# ALMOST4ALLMINI.net
KiCad netlist of a schematic drawn in EAGLE
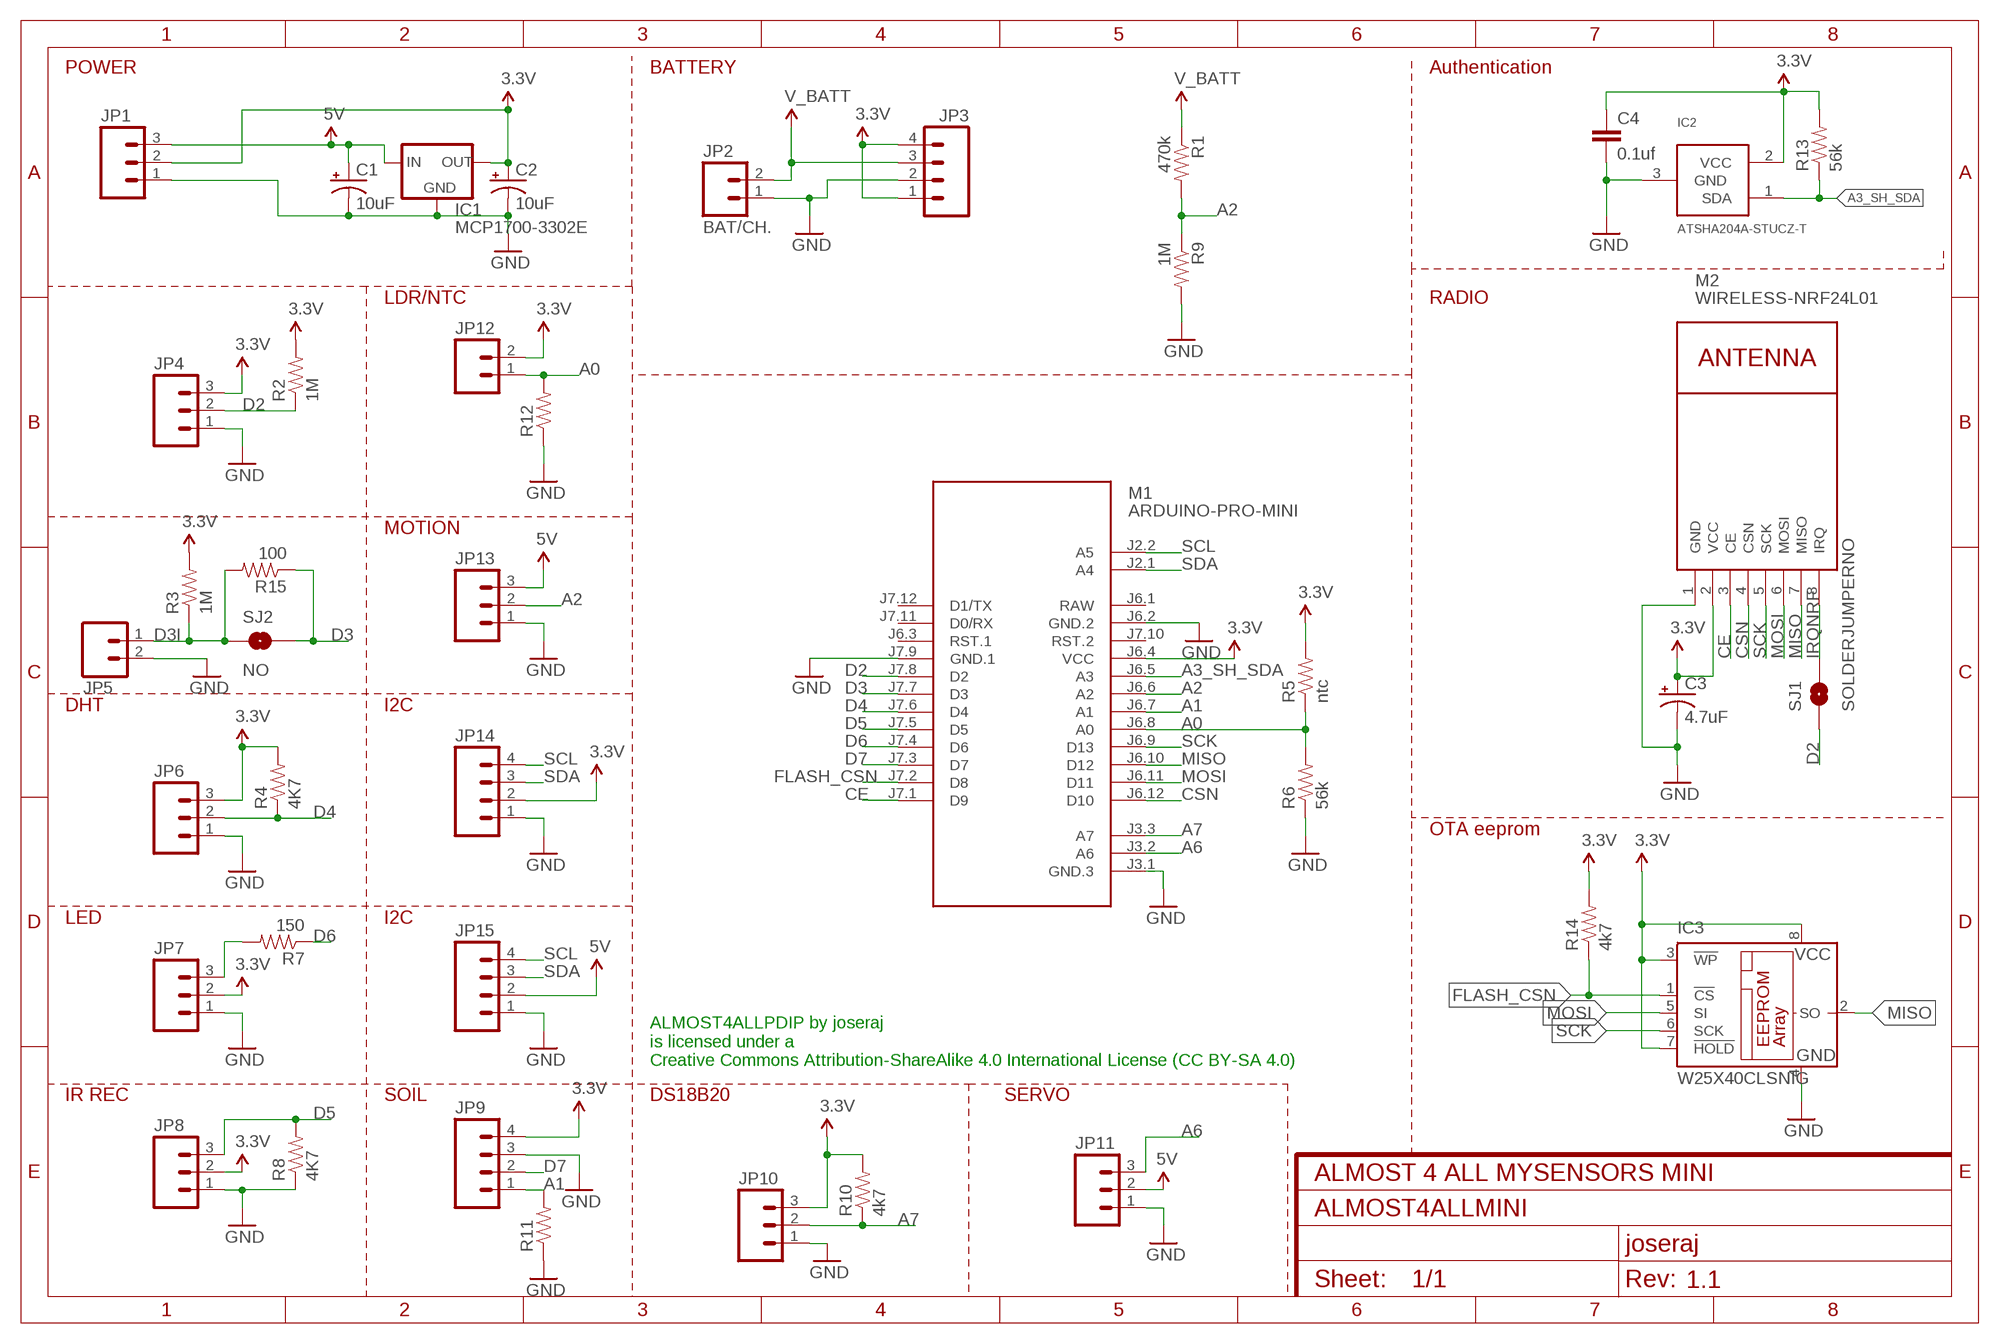
[diagram p0: schematic, sheet 1]

(export (version "E")
  (design (tool "Eeschema 10.0.6"))
  (components
    (comp (ref "C1")
      (value "10uF")
      (footprint "eagle-import:CPOL-RADIAL-10UF-25V")
      (libsource (lib "eagle-import") (part "CAP_POLPTH2"))
    )
    (comp (ref "C2")
      (value "10uF")
      (footprint "eagle-import:CPOL-RADIAL-10UF-25V")
      (libsource (lib "eagle-import") (part "CAP_POLPTH2"))
    )
    (comp (ref "C3")
      (value "4.7uF")
      (footprint "eagle-import:CPOL-RADIAL-10UF-25V")
      (libsource (lib "eagle-import") (part "CAP_POLPTH2"))
    )
    (comp (ref "C4")
      (value "0.1uf")
      (footprint "eagle-import:0805")
      (libsource (lib "eagle-import") (part "CAP0805"))
    )
    (comp (ref "IC1")
      (value "MCP1700-3302E")
      (footprint "eagle-import:TO92")
      (libsource (lib "eagle-import") (part "MCP1700TRI"))
    )
    (comp (ref "IC2")
      (value "ATSHA204A-STUCZ-T")
      (footprint "eagle-import:SOT23")
      (libsource (lib "eagle-import") (part "ATSHA204A"))
    )
    (comp (ref "IC3")
      (value "W25X40CLSNIG")
      (footprint "eagle-import:SO-08")
      (fields (field (name "MF") "MICROCHIP") (field (name "MPN") "25LC080/SN"))
      (libsource (lib "eagle-import") (part "25SNLC080"))
    )
    (comp (ref "JP1")
      (value "M03POLAR_LOCK")
      (footprint "eagle-import:MOLEX-1X3_LOCK")
      (libsource (lib "eagle-import") (part "M03POLAR_LOCK"))
    )
    (comp (ref "JP2")
      (value "BAT/CH.")
      (footprint "eagle-import:MOLEX-1X2_LOCK")
      (libsource (lib "eagle-import") (part "M02POLAR_LOCK"))
    )
    (comp (ref "JP3")
      (value "M04NO_SILK_ALL_ROUND")
      (footprint "eagle-import:1X04_NO_SILK_ALL_ROUND")
      (libsource (lib "eagle-import") (part "M04NO_SILK_ALL_ROUND"))
    )
    (comp (ref "JP4")
      (value "M03POLAR_LOCK")
      (footprint "eagle-import:MOLEX-1X3_LOCK")
      (libsource (lib "eagle-import") (part "M03POLAR_LOCK"))
    )
    (comp (ref "JP5")
      (value "M02POLAR_LOCK")
      (footprint "eagle-import:MOLEX-1X2_LOCK")
      (libsource (lib "eagle-import") (part "M02POLAR_LOCK"))
    )
    (comp (ref "JP6")
      (value "M03POLAR_LOCK")
      (footprint "eagle-import:MOLEX-1X3_LOCK")
      (libsource (lib "eagle-import") (part "M03POLAR_LOCK"))
    )
    (comp (ref "JP7")
      (value "M03POLAR_LOCK")
      (footprint "eagle-import:MOLEX-1X3_LOCK")
      (libsource (lib "eagle-import") (part "M03POLAR_LOCK"))
    )
    (comp (ref "JP8")
      (value "M03POLAR_LOCK")
      (footprint "eagle-import:MOLEX-1X3_LOCK")
      (libsource (lib "eagle-import") (part "M03POLAR_LOCK"))
    )
    (comp (ref "JP9")
      (value "M04POLAR_LOCK")
      (footprint "eagle-import:MOLEX-1X4_LOCK")
      (libsource (lib "eagle-import") (part "M04POLAR_LOCK"))
    )
    (comp (ref "JP10")
      (value "M03POLAR_LOCK")
      (footprint "eagle-import:MOLEX-1X3_LOCK")
      (libsource (lib "eagle-import") (part "M03POLAR_LOCK"))
    )
    (comp (ref "JP11")
      (value "M03POLAR_LOCK")
      (footprint "eagle-import:MOLEX-1X3_LOCK")
      (libsource (lib "eagle-import") (part "M03POLAR_LOCK"))
    )
    (comp (ref "JP12")
      (value "M02POLAR_LOCK")
      (footprint "eagle-import:MOLEX-1X2_LOCK")
      (libsource (lib "eagle-import") (part "M02POLAR_LOCK"))
    )
    (comp (ref "JP13")
      (value "M03POLAR_LOCK")
      (footprint "eagle-import:MOLEX-1X3_LOCK")
      (libsource (lib "eagle-import") (part "M03POLAR_LOCK"))
    )
    (comp (ref "JP14")
      (value "M04POLAR_LOCK")
      (footprint "eagle-import:MOLEX-1X4_LOCK")
      (libsource (lib "eagle-import") (part "M04POLAR_LOCK"))
    )
    (comp (ref "JP15")
      (value "M04POLAR_LOCK")
      (footprint "eagle-import:MOLEX-1X4_LOCK")
      (libsource (lib "eagle-import") (part "M04POLAR_LOCK"))
    )
    (comp (ref "M1")
      (value "ARDUINO-PRO-MINI")
      (footprint "eagle-import:ARDUINO-PRO-MINI#NP")
      (libsource (lib "eagle-import") (part "ARDUINO-PRO-MINI-#NP3.3V"))
    )
    (comp (ref "M2")
      (value "WIRELESS-NRF24L01")
      (footprint "eagle-import:WIRELESS-NRF24L01")
      (libsource (lib "eagle-import") (part "WIRELESS-NRF24L01"))
    )
    (comp (ref "R1")
      (value "470k")
      (footprint "eagle-import:0805")
      (libsource (lib "eagle-import") (part "RESISTOR0805-RES"))
    )
    (comp (ref "R2")
      (value "1M")
      (footprint "eagle-import:0805")
      (libsource (lib "eagle-import") (part "RESISTOR0805-RES"))
    )
    (comp (ref "R3")
      (value "1M")
      (footprint "eagle-import:0805")
      (libsource (lib "eagle-import") (part "RESISTOR0805-RES"))
    )
    (comp (ref "R4")
      (value "4K7")
      (footprint "eagle-import:0805")
      (libsource (lib "eagle-import") (part "RESISTOR0805-RES"))
    )
    (comp (ref "R5")
      (value "ntc")
      (footprint "eagle-import:0805")
      (libsource (lib "eagle-import") (part "RESISTOR0805-RES"))
    )
    (comp (ref "R6")
      (value "56k")
      (footprint "eagle-import:0805")
      (libsource (lib "eagle-import") (part "RESISTOR0805-RES"))
    )
    (comp (ref "R7")
      (value "150")
      (footprint "eagle-import:0805")
      (libsource (lib "eagle-import") (part "RESISTOR0805-RES"))
    )
    (comp (ref "R8")
      (value "4K7")
      (footprint "eagle-import:0805")
      (libsource (lib "eagle-import") (part "RESISTOR0805-RES"))
    )
    (comp (ref "R9")
      (value "1M")
      (footprint "eagle-import:0805")
      (libsource (lib "eagle-import") (part "RESISTOR0805-RES"))
    )
    (comp (ref "R10")
      (value "4k7")
      (footprint "eagle-import:0805")
      (libsource (lib "eagle-import") (part "RESISTOR0805-RES"))
    )
    (comp (ref "R11")
      (value "RESISTOR0805-RES")
      (footprint "eagle-import:0805")
      (libsource (lib "eagle-import") (part "RESISTOR0805-RES"))
    )
    (comp (ref "R12")
      (value "RESISTOR0805-RES")
      (footprint "eagle-import:0805")
      (libsource (lib "eagle-import") (part "RESISTOR0805-RES"))
    )
    (comp (ref "R13")
      (value "56k")
      (footprint "eagle-import:0805")
      (libsource (lib "eagle-import") (part "RESISTOR0805-RES"))
    )
    (comp (ref "R14")
      (value "4k7")
      (footprint "eagle-import:0805")
      (libsource (lib "eagle-import") (part "RESISTOR0805-RES"))
    )
    (comp (ref "R15")
      (value "100")
      (footprint "eagle-import:0805")
      (libsource (lib "eagle-import") (part "RESISTOR0805-RES"))
    )
    (comp (ref "SJ1")
      (value "SOLDERJUMPERNO")
      (footprint "eagle-import:SJ_2S-NO")
      (libsource (lib "eagle-import") (part "SOLDERJUMPERNO"))
    )
    (comp (ref "SJ2")
      (value "NO")
      (footprint "eagle-import:SJ_2S-NO")
      (libsource (lib "eagle-import") (part "SOLDERJUMPERNO"))
    )
  )
  (nets
    (net (code "1") (name "/A0") (class "Default")
      (node (ref "JP12") (pin "1") (pinfunction "1_1") (pintype "passive"))
      (node (ref "M1") (pin "J6.8") (pinfunction "A0_J6.8") (pintype "bidirectional"))
      (node (ref "R12") (pin "2") (pinfunction "2_2") (pintype "passive"))
      (node (ref "R5") (pin "1") (pinfunction "1_1") (pintype "passive"))
      (node (ref "R6") (pin "2") (pinfunction "2_2") (pintype "passive"))
    )
    (net (code "2") (name "/A1") (class "Default")
      (node (ref "JP9") (pin "1") (pinfunction "1_1") (pintype "passive"))
      (node (ref "M1") (pin "J6.7") (pinfunction "A1_J6.7") (pintype "bidirectional"))
      (node (ref "R11") (pin "2") (pinfunction "2_2") (pintype "passive"))
    )
    (net (code "3") (name "/A2") (class "Default")
      (node (ref "JP13") (pin "2") (pinfunction "2_2") (pintype "passive"))
      (node (ref "M1") (pin "J6.6") (pinfunction "A2_J6.6") (pintype "bidirectional"))
      (node (ref "R1") (pin "2") (pinfunction "2_2") (pintype "passive"))
      (node (ref "R9") (pin "1") (pinfunction "1_1") (pintype "passive"))
    )
    (net (code "4") (name "/A6") (class "Default")
      (node (ref "JP11") (pin "3") (pinfunction "3_3") (pintype "passive"))
      (node (ref "M1") (pin "J3.2") (pinfunction "A6_J3.2") (pintype "bidirectional"))
    )
    (net (code "5") (name "/A7") (class "Default")
      (node (ref "JP10") (pin "2") (pinfunction "2_2") (pintype "passive"))
      (node (ref "M1") (pin "J3.3") (pinfunction "A7_J3.3") (pintype "bidirectional"))
      (node (ref "R10") (pin "1") (pinfunction "1_1") (pintype "passive"))
    )
    (net (code "6") (name "/CE") (class "Default")
      (node (ref "M1") (pin "J7.1") (pinfunction "D9_J7.1") (pintype "bidirectional"))
      (node (ref "M2") (pin "3") (pinfunction "CE_3") (pintype "bidirectional"))
    )
    (net (code "7") (name "/CSN") (class "Default")
      (node (ref "M1") (pin "J6.12") (pinfunction "D10_J6.12") (pintype "bidirectional"))
      (node (ref "M2") (pin "4") (pinfunction "CSN_4") (pintype "bidirectional"))
    )
    (net (code "8") (name "/D2") (class "Default")
      (node (ref "JP4") (pin "2") (pinfunction "2_2") (pintype "passive"))
      (node (ref "M1") (pin "J7.8") (pinfunction "D2_J7.8") (pintype "bidirectional"))
      (node (ref "R2") (pin "1") (pinfunction "1_1") (pintype "passive"))
      (node (ref "SJ1") (pin "1") (pinfunction "1_1") (pintype "passive"))
    )
    (net (code "9") (name "/D3") (class "Default")
      (node (ref "M1") (pin "J7.7") (pinfunction "D3_J7.7") (pintype "bidirectional"))
      (node (ref "R15") (pin "1") (pinfunction "1_1") (pintype "passive"))
      (node (ref "SJ2") (pin "2") (pinfunction "2_2") (pintype "passive"))
    )
    (net (code "10") (name "/D3I") (class "Default")
      (node (ref "JP5") (pin "1") (pinfunction "1_1") (pintype "passive"))
      (node (ref "R15") (pin "2") (pinfunction "2_2") (pintype "passive"))
      (node (ref "R3") (pin "1") (pinfunction "1_1") (pintype "passive"))
      (node (ref "SJ2") (pin "1") (pinfunction "1_1") (pintype "passive"))
    )
    (net (code "11") (name "/D4") (class "Default")
      (node (ref "JP6") (pin "2") (pinfunction "2_2") (pintype "passive"))
      (node (ref "M1") (pin "J7.6") (pinfunction "D4_J7.6") (pintype "bidirectional"))
      (node (ref "R4") (pin "1") (pinfunction "1_1") (pintype "passive"))
    )
    (net (code "12") (name "/D5") (class "Default")
      (node (ref "JP8") (pin "3") (pinfunction "3_3") (pintype "passive"))
      (node (ref "M1") (pin "J7.5") (pinfunction "D5_J7.5") (pintype "bidirectional"))
      (node (ref "R8") (pin "2") (pinfunction "2_2") (pintype "passive"))
    )
    (net (code "13") (name "/D6") (class "Default")
      (node (ref "M1") (pin "J7.4") (pinfunction "D6_J7.4") (pintype "bidirectional"))
      (node (ref "R7") (pin "1") (pinfunction "1_1") (pintype "passive"))
    )
    (net (code "14") (name "/D7") (class "Default")
      (node (ref "JP9") (pin "2") (pinfunction "2_2") (pintype "passive"))
      (node (ref "M1") (pin "J7.3") (pinfunction "D7_J7.3") (pintype "bidirectional"))
    )
    (net (code "15") (name "/IRQNRF") (class "Default")
      (node (ref "M2") (pin "8") (pinfunction "IRQ_8") (pintype "bidirectional"))
      (node (ref "SJ1") (pin "2") (pinfunction "2_2") (pintype "passive"))
    )
    (net (code "16") (name "/RAW") (class "Default")
      (node (ref "M1") (pin "J6.1") (pinfunction "RAW_J6.1") (pintype "power_in"))
    )
    (net (code "17") (name "/SCL") (class "Default")
      (node (ref "JP14") (pin "4") (pinfunction "4_4") (pintype "passive"))
      (node (ref "JP15") (pin "4") (pinfunction "4_4") (pintype "passive"))
      (node (ref "M1") (pin "J2.2") (pinfunction "A5_J2.2") (pintype "bidirectional"))
    )
    (net (code "18") (name "/SDA") (class "Default")
      (node (ref "JP14") (pin "3") (pinfunction "3_3") (pintype "passive"))
      (node (ref "JP15") (pin "3") (pinfunction "3_3") (pintype "passive"))
      (node (ref "M1") (pin "J2.1") (pinfunction "A4_J2.1") (pintype "bidirectional"))
    )
    (net (code "19") (name "3.3V") (class "Default")
      (node (ref "C2") (pin "1") (pinfunction "+_1") (pintype "passive"))
      (node (ref "C3") (pin "1") (pinfunction "+_1") (pintype "passive"))
      (node (ref "C4") (pin "1") (pinfunction "1_1") (pintype "passive"))
      (node (ref "IC1") (pin "3") (pinfunction "OUT_3") (pintype "passive"))
      (node (ref "IC2") (pin "2") (pinfunction "VCC_2") (pintype "bidirectional"))
      (node (ref "IC3") (pin "3") (pinfunction "~{WP}_3") (pintype "input"))
      (node (ref "IC3") (pin "7") (pinfunction "~{HOLD}_7") (pintype "input"))
      (node (ref "IC3") (pin "8") (pinfunction "VCC_8") (pintype "power_in"))
      (node (ref "JP1") (pin "2") (pinfunction "2_2") (pintype "passive"))
      (node (ref "JP10") (pin "3") (pinfunction "3_3") (pintype "passive"))
      (node (ref "JP12") (pin "2") (pinfunction "2_2") (pintype "passive"))
      (node (ref "JP14") (pin "2") (pinfunction "2_2") (pintype "passive"))
      (node (ref "JP3") (pin "1") (pinfunction "1_1") (pintype "passive"))
      (node (ref "JP3") (pin "4") (pinfunction "4_4") (pintype "passive"))
      (node (ref "JP4") (pin "3") (pinfunction "3_3") (pintype "passive"))
      (node (ref "JP6") (pin "3") (pinfunction "3_3") (pintype "passive"))
      (node (ref "JP7") (pin "2") (pinfunction "2_2") (pintype "passive"))
      (node (ref "JP8") (pin "2") (pinfunction "2_2") (pintype "passive"))
      (node (ref "JP9") (pin "4") (pinfunction "4_4") (pintype "passive"))
      (node (ref "M1") (pin "J6.4") (pinfunction "VCC_J6.4") (pintype "power_in"))
      (node (ref "M2") (pin "2") (pinfunction "VCC_2") (pintype "power_in"))
      (node (ref "R10") (pin "2") (pinfunction "2_2") (pintype "passive"))
      (node (ref "R13") (pin "2") (pinfunction "2_2") (pintype "passive"))
      (node (ref "R14") (pin "2") (pinfunction "2_2") (pintype "passive"))
      (node (ref "R2") (pin "2") (pinfunction "2_2") (pintype "passive"))
      (node (ref "R3") (pin "2") (pinfunction "2_2") (pintype "passive"))
      (node (ref "R4") (pin "2") (pinfunction "2_2") (pintype "passive"))
      (node (ref "R5") (pin "2") (pinfunction "2_2") (pintype "passive"))
    )
    (net (code "20") (name "5V") (class "Default")
      (node (ref "C1") (pin "1") (pinfunction "+_1") (pintype "passive"))
      (node (ref "IC1") (pin "2") (pinfunction "IN_2") (pintype "input"))
      (node (ref "JP1") (pin "3") (pinfunction "3_3") (pintype "passive"))
      (node (ref "JP11") (pin "2") (pinfunction "2_2") (pintype "passive"))
      (node (ref "JP13") (pin "3") (pinfunction "3_3") (pintype "passive"))
      (node (ref "JP15") (pin "2") (pinfunction "2_2") (pintype "passive"))
    )
    (net (code "21") (name "A3_SH_SDA") (class "Default")
      (node (ref "IC2") (pin "1") (pinfunction "SDA_1") (pintype "bidirectional"))
      (node (ref "M1") (pin "J6.5") (pinfunction "A3_J6.5") (pintype "bidirectional"))
      (node (ref "R13") (pin "1") (pinfunction "1_1") (pintype "passive"))
    )
    (net (code "22") (name "FLASH_CSN") (class "Default")
      (node (ref "IC3") (pin "1") (pinfunction "~{CS}_1") (pintype "input"))
      (node (ref "M1") (pin "J7.2") (pinfunction "D8_J7.2") (pintype "bidirectional"))
      (node (ref "R14") (pin "1") (pinfunction "1_1") (pintype "passive"))
    )
    (net (code "23") (name "GND") (class "Default")
      (node (ref "C1") (pin "2") (pinfunction "-_2") (pintype "passive"))
      (node (ref "C2") (pin "2") (pinfunction "-_2") (pintype "passive"))
      (node (ref "C3") (pin "2") (pinfunction "-_2") (pintype "passive"))
      (node (ref "C4") (pin "2") (pinfunction "2_2") (pintype "passive"))
      (node (ref "IC1") (pin "1") (pinfunction "GND_1") (pintype "input"))
      (node (ref "IC2") (pin "3") (pinfunction "GND_3") (pintype "bidirectional"))
      (node (ref "IC3") (pin "4") (pinfunction "GND_4") (pintype "power_in"))
      (node (ref "JP1") (pin "1") (pinfunction "1_1") (pintype "passive"))
      (node (ref "JP10") (pin "1") (pinfunction "1_1") (pintype "passive"))
      (node (ref "JP11") (pin "1") (pinfunction "1_1") (pintype "passive"))
      (node (ref "JP13") (pin "1") (pinfunction "1_1") (pintype "passive"))
      (node (ref "JP14") (pin "1") (pinfunction "1_1") (pintype "passive"))
      (node (ref "JP15") (pin "1") (pinfunction "1_1") (pintype "passive"))
      (node (ref "JP2") (pin "1") (pinfunction "1_1") (pintype "passive"))
      (node (ref "JP3") (pin "2") (pinfunction "2_2") (pintype "passive"))
      (node (ref "JP4") (pin "1") (pinfunction "1_1") (pintype "passive"))
      (node (ref "JP5") (pin "2") (pinfunction "2_2") (pintype "passive"))
      (node (ref "JP6") (pin "1") (pinfunction "1_1") (pintype "passive"))
      (node (ref "JP7") (pin "1") (pinfunction "1_1") (pintype "passive"))
      (node (ref "JP8") (pin "1") (pinfunction "1_1") (pintype "passive"))
      (node (ref "JP9") (pin "3") (pinfunction "3_3") (pintype "passive"))
      (node (ref "M1") (pin "J3.1") (pinfunction "GND.3_J3.1") (pintype "bidirectional"))
      (node (ref "M1") (pin "J6.2") (pinfunction "GND.2_J6.2") (pintype "power_in"))
      (node (ref "M1") (pin "J7.9") (pinfunction "GND.1_J7.9") (pintype "power_in"))
      (node (ref "M2") (pin "1") (pinfunction "GND_1") (pintype "power_in"))
      (node (ref "R11") (pin "1") (pinfunction "1_1") (pintype "passive"))
      (node (ref "R12") (pin "1") (pinfunction "1_1") (pintype "passive"))
      (node (ref "R6") (pin "1") (pinfunction "1_1") (pintype "passive"))
      (node (ref "R8") (pin "1") (pinfunction "1_1") (pintype "passive"))
      (node (ref "R9") (pin "2") (pinfunction "2_2") (pintype "passive"))
    )
    (net (code "24") (name "MISO") (class "Default")
      (node (ref "IC3") (pin "2") (pinfunction "SO_2") (pintype "bidirectional"))
      (node (ref "M1") (pin "J6.10") (pinfunction "D12_J6.10") (pintype "bidirectional"))
      (node (ref "M2") (pin "7") (pinfunction "MISO_7") (pintype "bidirectional"))
    )
    (net (code "25") (name "MOSI") (class "Default")
      (node (ref "IC3") (pin "5") (pinfunction "SI_5") (pintype "input"))
      (node (ref "M1") (pin "J6.11") (pinfunction "D11_J6.11") (pintype "bidirectional"))
      (node (ref "M2") (pin "6") (pinfunction "MOSI_6") (pintype "bidirectional"))
    )
    (net (code "26") (name "Net-(JP7-Pad3)") (class "Default")
      (node (ref "JP7") (pin "3") (pinfunction "3_3") (pintype "passive"))
      (node (ref "R7") (pin "2") (pinfunction "2_2") (pintype "passive"))
    )
    (net (code "27") (name "SCK") (class "Default")
      (node (ref "IC3") (pin "6") (pinfunction "SCK_6") (pintype "input"))
      (node (ref "M1") (pin "J6.9") (pinfunction "D13_J6.9") (pintype "bidirectional"))
      (node (ref "M2") (pin "5") (pinfunction "SCK_5") (pintype "bidirectional"))
    )
    (net (code "28") (name "V_BATT") (class "Default")
      (node (ref "JP2") (pin "2") (pinfunction "2_2") (pintype "passive"))
      (node (ref "JP3") (pin "3") (pinfunction "3_3") (pintype "passive"))
      (node (ref "R1") (pin "1") (pinfunction "1_1") (pintype "passive"))
    )
    (net (code "29") (name "unconnected-(M1-D0{slash}RX-PadJ7.11)") (class "Default")
      (node (ref "M1") (pin "J7.11") (pinfunction "D0/RX_J7.11") (pintype "bidirectional"))
    )
    (net (code "30") (name "unconnected-(M1-D1{slash}TX-PadJ7.12)") (class "Default")
      (node (ref "M1") (pin "J7.12") (pinfunction "D1/TX_J7.12") (pintype "bidirectional"))
    )
    (net (code "31") (name "unconnected-(M1-RST.1-PadJ6.3)") (class "Default")
      (node (ref "M1") (pin "J6.3") (pinfunction "RST.1_J6.3") (pintype "bidirectional"))
    )
    (net (code "32") (name "unconnected-(M1-RST.2-PadJ7.10)") (class "Default")
      (node (ref "M1") (pin "J7.10") (pinfunction "RST.2_J7.10") (pintype "bidirectional"))
    )
  )
)
